# 2SlotElevator.net
KiCad netlist of a schematic drawn in Altium Designer
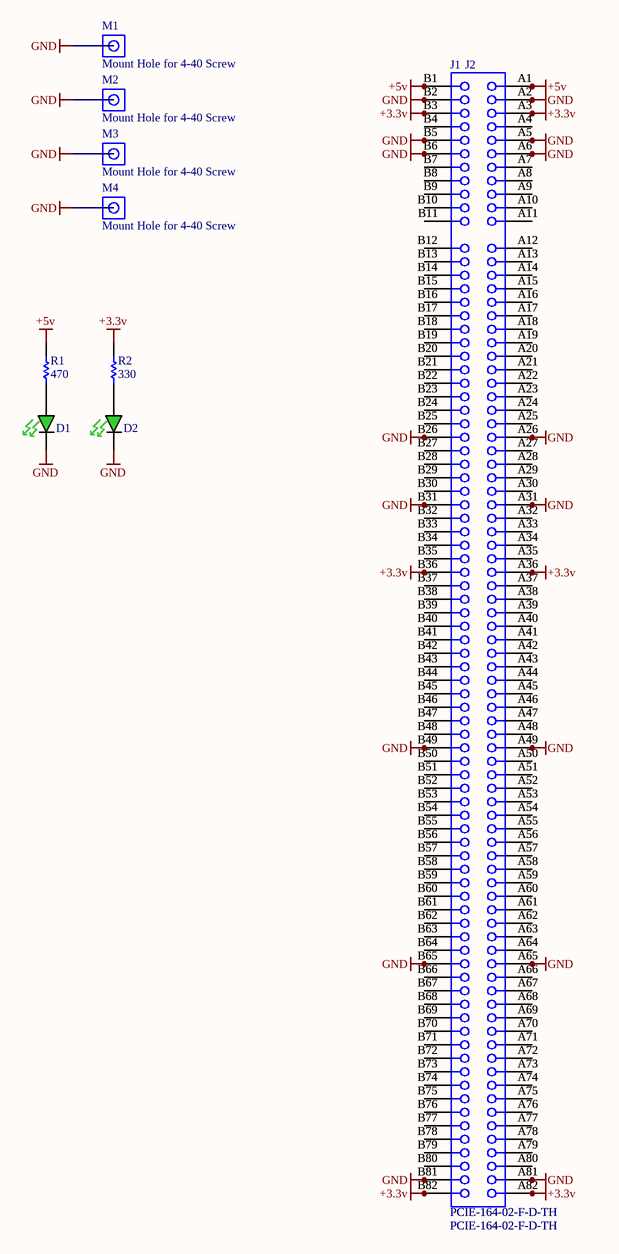
[diagram p0: 2SlotElevator.SchDoc]

(export (version "E")
  (design (tool "Eeschema 10.0.6"))
  (components
    (comp (ref "D1")
      (value "LED 3X1.5MM 568NM GN WTR CLR SMD")
      (footprint "LED_1206 - GREEN")
      (fields
        (field (name "MANUFACTURER") "Kingbright Corp")
        (field (name "MANUFACTURER PART NUMBER") "APL3015SGC-F01")
      )
      (libsource (lib "Diode") (part "APL3015SGC-F01"))
    )
    (comp (ref "D2")
      (value "LED 3X1.5MM 568NM GN WTR CLR SMD")
      (footprint "LED_1206 - GREEN")
      (fields
        (field (name "MANUFACTURER") "Kingbright Corp")
        (field (name "MANUFACTURER PART NUMBER") "APL3015SGC-F01")
      )
      (libsource (lib "Diode") (part "APL3015SGC-F01"))
    )
    (comp (ref "J1")
      (value "PCIE-164-02-F-D-TH")
      (footprint "PCIE-164-02-F-D-TH")
      (description "SAMTEC - PCIE-164-02-F-D-TH - SOCKET, PCI-E, 2X82")
      (fields (field (name "MANUFACTURER") "SAMTEC") (field (name "ALTIUM_VALUE") "PCIE-164-02-F-D-TH"))
      (libsource (lib "eConnector") (part "PCIE-164-02-F-D-TH"))
    )
    (comp (ref "J2")
      (value "PCIE-164-02-F-D-TH")
      (footprint "PCIE-164-02-F-D-TH")
      (description "SAMTEC - PCIE-164-02-F-D-TH - SOCKET, PCI-E, 2X82")
      (fields (field (name "MANUFACTURER") "SAMTEC") (field (name "ALTIUM_VALUE") "PCIE-164-02-F-D-TH"))
      (libsource (lib "eConnector") (part "PCIE-164-02-F-D-TH"))
    )
    (comp (ref "M1")
      (value "Mount Hole for 4-40 Screw")
      (footprint "4-40 Hole")
      (fields (field (name "SOURCE") "Digikey"))
      (libsource (lib "EMechanical") (part "4-40 Hole"))
    )
    (comp (ref "M2")
      (value "Mount Hole for 4-40 Screw")
      (footprint "4-40 Hole")
      (fields (field (name "SOURCE") "Digikey"))
      (libsource (lib "EMechanical") (part "4-40 Hole"))
    )
    (comp (ref "M3")
      (value "Mount Hole for 4-40 Screw")
      (footprint "4-40 Hole")
      (fields (field (name "SOURCE") "Digikey"))
      (libsource (lib "EMechanical") (part "4-40 Hole"))
    )
    (comp (ref "M4")
      (value "Mount Hole for 4-40 Screw")
      (footprint "4-40 Hole")
      (fields (field (name "SOURCE") "Digikey"))
      (libsource (lib "EMechanical") (part "4-40 Hole"))
    )
    (comp (ref "R1")
      (value "470")
      (footprint "R0603")
      (description "RES 470 OHM 1/10W 1% 0603 SMD")
      (fields
        (field (name "MANUFACTURER") "Panasonic - ECG")
        (field (name "MANUFACTURER PART NUMBER") "ERJ-3EKF4700V")
      )
      (libsource (lib "eRCL") (part "ERJ-3EKF4700V"))
    )
    (comp (ref "R2")
      (value "330")
      (footprint "R0603")
      (description "RES 330 OHM 1/10W 1% 0603 SMD")
      (fields
        (field (name "MANUFACTURER") "Panasonic - ECG")
        (field (name "MANUFACTURER PART NUMBER") "ERJ-3EKF3300V")
      )
      (libsource (lib "eRCL") (part "ERJ-3EKF3300V"))
    )
  )
  (nets
    (net (code "1") (name "+3.3v") (class "Default")
      (node (ref "J1") (pin "A3") (pinfunction "A3_A3") (pintype "passive"))
      (node (ref "J1") (pin "A36") (pinfunction "A36_A36") (pintype "passive"))
      (node (ref "J1") (pin "A82") (pinfunction "A82_A82") (pintype "passive"))
      (node (ref "J1") (pin "B3") (pinfunction "B3_B3") (pintype "passive"))
      (node (ref "J1") (pin "B36") (pinfunction "B36_B36") (pintype "passive"))
      (node (ref "J1") (pin "B82") (pinfunction "B82_B82") (pintype "passive"))
      (node (ref "J2") (pin "A3") (pinfunction "A3_A3") (pintype "passive"))
      (node (ref "J2") (pin "A36") (pinfunction "A36_A36") (pintype "passive"))
      (node (ref "J2") (pin "A82") (pinfunction "A82_A82") (pintype "passive"))
      (node (ref "J2") (pin "B3") (pinfunction "B3_B3") (pintype "passive"))
      (node (ref "J2") (pin "B36") (pinfunction "B36_B36") (pintype "passive"))
      (node (ref "J2") (pin "B82") (pinfunction "B82_B82") (pintype "passive"))
      (node (ref "R2") (pin "2") (pinfunction "2_2") (pintype "passive"))
    )
    (net (code "2") (name "+5v") (class "Default")
      (node (ref "J1") (pin "A1") (pinfunction "A1_A1") (pintype "passive"))
      (node (ref "J1") (pin "B1") (pinfunction "B1_B1") (pintype "passive"))
      (node (ref "J2") (pin "A1") (pinfunction "A1_A1") (pintype "passive"))
      (node (ref "J2") (pin "B1") (pinfunction "B1_B1") (pintype "passive"))
      (node (ref "R1") (pin "2") (pinfunction "2_2") (pintype "passive"))
    )
    (net (code "3") (name "GND") (class "Default")
      (node (ref "D1") (pin "C") (pinfunction "C_C") (pintype "passive"))
      (node (ref "D2") (pin "C") (pinfunction "C_C") (pintype "passive"))
      (node (ref "J1") (pin "A2") (pinfunction "A2_A2") (pintype "passive"))
      (node (ref "J1") (pin "A26") (pinfunction "A26_A26") (pintype "passive"))
      (node (ref "J1") (pin "A31") (pinfunction "A31_A31") (pintype "passive"))
      (node (ref "J1") (pin "A49") (pinfunction "A49_A49") (pintype "passive"))
      (node (ref "J1") (pin "A5") (pinfunction "A5_A5") (pintype "passive"))
      (node (ref "J1") (pin "A6") (pinfunction "A6_A6") (pintype "passive"))
      (node (ref "J1") (pin "A65") (pinfunction "A65_A65") (pintype "passive"))
      (node (ref "J1") (pin "A81") (pinfunction "A81_A81") (pintype "passive"))
      (node (ref "J1") (pin "B2") (pinfunction "B2_B2") (pintype "passive"))
      (node (ref "J1") (pin "B26") (pinfunction "B26_B26") (pintype "passive"))
      (node (ref "J1") (pin "B31") (pinfunction "B31_B31") (pintype "passive"))
      (node (ref "J1") (pin "B49") (pinfunction "B49_B49") (pintype "passive"))
      (node (ref "J1") (pin "B5") (pinfunction "B5_B5") (pintype "passive"))
      (node (ref "J1") (pin "B6") (pinfunction "B6_B6") (pintype "passive"))
      (node (ref "J1") (pin "B65") (pinfunction "B65_B65") (pintype "passive"))
      (node (ref "J1") (pin "B81") (pinfunction "B81_B81") (pintype "passive"))
      (node (ref "J2") (pin "A2") (pinfunction "A2_A2") (pintype "passive"))
      (node (ref "J2") (pin "A26") (pinfunction "A26_A26") (pintype "passive"))
      (node (ref "J2") (pin "A31") (pinfunction "A31_A31") (pintype "passive"))
      (node (ref "J2") (pin "A49") (pinfunction "A49_A49") (pintype "passive"))
      (node (ref "J2") (pin "A5") (pinfunction "A5_A5") (pintype "passive"))
      (node (ref "J2") (pin "A6") (pinfunction "A6_A6") (pintype "passive"))
      (node (ref "J2") (pin "A65") (pinfunction "A65_A65") (pintype "passive"))
      (node (ref "J2") (pin "A81") (pinfunction "A81_A81") (pintype "passive"))
      (node (ref "J2") (pin "B2") (pinfunction "B2_B2") (pintype "passive"))
      (node (ref "J2") (pin "B26") (pinfunction "B26_B26") (pintype "passive"))
      (node (ref "J2") (pin "B31") (pinfunction "B31_B31") (pintype "passive"))
      (node (ref "J2") (pin "B49") (pinfunction "B49_B49") (pintype "passive"))
      (node (ref "J2") (pin "B5") (pinfunction "B5_B5") (pintype "passive"))
      (node (ref "J2") (pin "B6") (pinfunction "B6_B6") (pintype "passive"))
      (node (ref "J2") (pin "B65") (pinfunction "B65_B65") (pintype "passive"))
      (node (ref "J2") (pin "B81") (pinfunction "B81_B81") (pintype "passive"))
      (node (ref "M1") (pin "1") (pinfunction "1_1") (pintype "passive"))
      (node (ref "M2") (pin "1") (pinfunction "1_1") (pintype "passive"))
      (node (ref "M3") (pin "1") (pinfunction "1_1") (pintype "passive"))
      (node (ref "M4") (pin "1") (pinfunction "1_1") (pintype "passive"))
    )
    (net (code "4") (name "Net-(D1-PadA)") (class "Default")
      (node (ref "D1") (pin "A") (pinfunction "A_A") (pintype "passive"))
      (node (ref "R1") (pin "1") (pinfunction "1_1") (pintype "passive"))
    )
    (net (code "5") (name "Net-(D2-PadA)") (class "Default")
      (node (ref "D2") (pin "A") (pinfunction "A_A") (pintype "passive"))
      (node (ref "R2") (pin "1") (pinfunction "1_1") (pintype "passive"))
    )
    (net (code "6") (name "Net-(J1-PadA4)") (class "Default")
      (node (ref "J1") (pin "A4") (pinfunction "A4_A4") (pintype "passive"))
      (node (ref "J2") (pin "A4") (pinfunction "A4_A4") (pintype "passive"))
    )
    (net (code "7") (name "Net-(J1-PadA7)") (class "Default")
      (node (ref "J1") (pin "A7") (pinfunction "A7_A7") (pintype "passive"))
      (node (ref "J2") (pin "A7") (pinfunction "A7_A7") (pintype "passive"))
    )
    (net (code "8") (name "Net-(J1-PadA8)") (class "Default")
      (node (ref "J1") (pin "A8") (pinfunction "A8_A8") (pintype "passive"))
      (node (ref "J2") (pin "A8") (pinfunction "A8_A8") (pintype "passive"))
    )
    (net (code "9") (name "Net-(J1-PadA9)") (class "Default")
      (node (ref "J1") (pin "A9") (pinfunction "A9_A9") (pintype "passive"))
      (node (ref "J2") (pin "A9") (pinfunction "A9_A9") (pintype "passive"))
    )
    (net (code "10") (name "Net-(J1-PadA10)") (class "Default")
      (node (ref "J1") (pin "A10") (pinfunction "A10_A10") (pintype "passive"))
      (node (ref "J2") (pin "A10") (pinfunction "A10_A10") (pintype "passive"))
    )
    (net (code "11") (name "Net-(J1-PadA11)") (class "Default")
      (node (ref "J1") (pin "A11") (pinfunction "A11_A11") (pintype "passive"))
      (node (ref "J2") (pin "A11") (pinfunction "A11_A11") (pintype "passive"))
    )
    (net (code "12") (name "Net-(J1-PadA12)") (class "Default")
      (node (ref "J1") (pin "A12") (pinfunction "A12_A12") (pintype "passive"))
      (node (ref "J2") (pin "A12") (pinfunction "A12_A12") (pintype "passive"))
    )
    (net (code "13") (name "Net-(J1-PadA13)") (class "Default")
      (node (ref "J1") (pin "A13") (pinfunction "A13_A13") (pintype "passive"))
      (node (ref "J2") (pin "A13") (pinfunction "A13_A13") (pintype "passive"))
    )
    (net (code "14") (name "Net-(J1-PadA14)") (class "Default")
      (node (ref "J1") (pin "A14") (pinfunction "A14_A14") (pintype "passive"))
      (node (ref "J2") (pin "A14") (pinfunction "A14_A14") (pintype "passive"))
    )
    (net (code "15") (name "Net-(J1-PadA15)") (class "Default")
      (node (ref "J1") (pin "A15") (pinfunction "A15_A15") (pintype "passive"))
      (node (ref "J2") (pin "A15") (pinfunction "A15_A15") (pintype "passive"))
    )
    (net (code "16") (name "Net-(J1-PadA16)") (class "Default")
      (node (ref "J1") (pin "A16") (pinfunction "A16_A16") (pintype "passive"))
      (node (ref "J2") (pin "A16") (pinfunction "A16_A16") (pintype "passive"))
    )
    (net (code "17") (name "Net-(J1-PadA17)") (class "Default")
      (node (ref "J1") (pin "A17") (pinfunction "A17_A17") (pintype "passive"))
      (node (ref "J2") (pin "A17") (pinfunction "A17_A17") (pintype "passive"))
    )
    (net (code "18") (name "Net-(J1-PadA18)") (class "Default")
      (node (ref "J1") (pin "A18") (pinfunction "A18_A18") (pintype "passive"))
      (node (ref "J2") (pin "A18") (pinfunction "A18_A18") (pintype "passive"))
    )
    (net (code "19") (name "Net-(J1-PadA19)") (class "Default")
      (node (ref "J1") (pin "A19") (pinfunction "A19_A19") (pintype "passive"))
      (node (ref "J2") (pin "A19") (pinfunction "A19_A19") (pintype "passive"))
    )
    (net (code "20") (name "Net-(J1-PadA20)") (class "Default")
      (node (ref "J1") (pin "A20") (pinfunction "A20_A20") (pintype "passive"))
      (node (ref "J2") (pin "A20") (pinfunction "A20_A20") (pintype "passive"))
    )
    (net (code "21") (name "Net-(J1-PadA21)") (class "Default")
      (node (ref "J1") (pin "A21") (pinfunction "A21_A21") (pintype "passive"))
      (node (ref "J2") (pin "A21") (pinfunction "A21_A21") (pintype "passive"))
    )
    (net (code "22") (name "Net-(J1-PadA22)") (class "Default")
      (node (ref "J1") (pin "A22") (pinfunction "A22_A22") (pintype "passive"))
      (node (ref "J2") (pin "A22") (pinfunction "A22_A22") (pintype "passive"))
    )
    (net (code "23") (name "Net-(J1-PadA23)") (class "Default")
      (node (ref "J1") (pin "A23") (pinfunction "A23_A23") (pintype "passive"))
      (node (ref "J2") (pin "A23") (pinfunction "A23_A23") (pintype "passive"))
    )
    (net (code "24") (name "Net-(J1-PadA24)") (class "Default")
      (node (ref "J1") (pin "A24") (pinfunction "A24_A24") (pintype "passive"))
      (node (ref "J2") (pin "A24") (pinfunction "A24_A24") (pintype "passive"))
    )
    (net (code "25") (name "Net-(J1-PadA25)") (class "Default")
      (node (ref "J1") (pin "A25") (pinfunction "A25_A25") (pintype "passive"))
      (node (ref "J2") (pin "A25") (pinfunction "A25_A25") (pintype "passive"))
    )
    (net (code "26") (name "Net-(J1-PadA27)") (class "Default")
      (node (ref "J1") (pin "A27") (pinfunction "A27_A27") (pintype "passive"))
      (node (ref "J2") (pin "A27") (pinfunction "A27_A27") (pintype "passive"))
    )
    (net (code "27") (name "Net-(J1-PadA28)") (class "Default")
      (node (ref "J1") (pin "A28") (pinfunction "A28_A28") (pintype "passive"))
      (node (ref "J2") (pin "A28") (pinfunction "A28_A28") (pintype "passive"))
    )
    (net (code "28") (name "Net-(J1-PadA29)") (class "Default")
      (node (ref "J1") (pin "A29") (pinfunction "A29_A29") (pintype "passive"))
      (node (ref "J2") (pin "A29") (pinfunction "A29_A29") (pintype "passive"))
    )
    (net (code "29") (name "Net-(J1-PadA30)") (class "Default")
      (node (ref "J1") (pin "A30") (pinfunction "A30_A30") (pintype "passive"))
      (node (ref "J2") (pin "A30") (pinfunction "A30_A30") (pintype "passive"))
    )
    (net (code "30") (name "Net-(J1-PadA32)") (class "Default")
      (node (ref "J1") (pin "A32") (pinfunction "A32_A32") (pintype "passive"))
      (node (ref "J2") (pin "A32") (pinfunction "A32_A32") (pintype "passive"))
    )
    (net (code "31") (name "Net-(J1-PadA33)") (class "Default")
      (node (ref "J1") (pin "A33") (pinfunction "A33_A33") (pintype "passive"))
      (node (ref "J2") (pin "A33") (pinfunction "A33_A33") (pintype "passive"))
    )
    (net (code "32") (name "Net-(J1-PadA34)") (class "Default")
      (node (ref "J1") (pin "A34") (pinfunction "A34_A34") (pintype "passive"))
      (node (ref "J2") (pin "A34") (pinfunction "A34_A34") (pintype "passive"))
    )
    (net (code "33") (name "Net-(J1-PadA35)") (class "Default")
      (node (ref "J1") (pin "A35") (pinfunction "A35_A35") (pintype "passive"))
      (node (ref "J2") (pin "A35") (pinfunction "A35_A35") (pintype "passive"))
    )
    (net (code "34") (name "Net-(J1-PadA37)") (class "Default")
      (node (ref "J1") (pin "A37") (pinfunction "A37_A37") (pintype "passive"))
      (node (ref "J2") (pin "A37") (pinfunction "A37_A37") (pintype "passive"))
    )
    (net (code "35") (name "Net-(J1-PadA38)") (class "Default")
      (node (ref "J1") (pin "A38") (pinfunction "A38_A38") (pintype "passive"))
      (node (ref "J2") (pin "A38") (pinfunction "A38_A38") (pintype "passive"))
    )
    (net (code "36") (name "Net-(J1-PadA39)") (class "Default")
      (node (ref "J1") (pin "A39") (pinfunction "A39_A39") (pintype "passive"))
      (node (ref "J2") (pin "A39") (pinfunction "A39_A39") (pintype "passive"))
    )
    (net (code "37") (name "Net-(J1-PadA40)") (class "Default")
      (node (ref "J1") (pin "A40") (pinfunction "A40_A40") (pintype "passive"))
      (node (ref "J2") (pin "A40") (pinfunction "A40_A40") (pintype "passive"))
    )
    (net (code "38") (name "Net-(J1-PadA41)") (class "Default")
      (node (ref "J1") (pin "A41") (pinfunction "A41_A41") (pintype "passive"))
      (node (ref "J2") (pin "A41") (pinfunction "A41_A41") (pintype "passive"))
    )
    (net (code "39") (name "Net-(J1-PadA42)") (class "Default")
      (node (ref "J1") (pin "A42") (pinfunction "A42_A42") (pintype "passive"))
      (node (ref "J2") (pin "A42") (pinfunction "A42_A42") (pintype "passive"))
    )
    (net (code "40") (name "Net-(J1-PadA43)") (class "Default")
      (node (ref "J1") (pin "A43") (pinfunction "A43_A43") (pintype "passive"))
      (node (ref "J2") (pin "A43") (pinfunction "A43_A43") (pintype "passive"))
    )
    (net (code "41") (name "Net-(J1-PadA44)") (class "Default")
      (node (ref "J1") (pin "A44") (pinfunction "A44_A44") (pintype "passive"))
      (node (ref "J2") (pin "A44") (pinfunction "A44_A44") (pintype "passive"))
    )
    (net (code "42") (name "Net-(J1-PadA45)") (class "Default")
      (node (ref "J1") (pin "A45") (pinfunction "A45_A45") (pintype "passive"))
      (node (ref "J2") (pin "A45") (pinfunction "A45_A45") (pintype "passive"))
    )
    (net (code "43") (name "Net-(J1-PadA46)") (class "Default")
      (node (ref "J1") (pin "A46") (pinfunction "A46_A46") (pintype "passive"))
      (node (ref "J2") (pin "A46") (pinfunction "A46_A46") (pintype "passive"))
    )
    (net (code "44") (name "Net-(J1-PadA47)") (class "Default")
      (node (ref "J1") (pin "A47") (pinfunction "A47_A47") (pintype "passive"))
      (node (ref "J2") (pin "A47") (pinfunction "A47_A47") (pintype "passive"))
    )
    (net (code "45") (name "Net-(J1-PadA48)") (class "Default")
      (node (ref "J1") (pin "A48") (pinfunction "A48_A48") (pintype "passive"))
      (node (ref "J2") (pin "A48") (pinfunction "A48_A48") (pintype "passive"))
    )
    (net (code "46") (name "Net-(J1-PadA50)") (class "Default")
      (node (ref "J1") (pin "A50") (pinfunction "A50_A50") (pintype "passive"))
      (node (ref "J2") (pin "A50") (pinfunction "A50_A50") (pintype "passive"))
    )
    (net (code "47") (name "Net-(J1-PadA51)") (class "Default")
      (node (ref "J1") (pin "A51") (pinfunction "A51_A51") (pintype "passive"))
      (node (ref "J2") (pin "A51") (pinfunction "A51_A51") (pintype "passive"))
    )
    (net (code "48") (name "Net-(J1-PadA52)") (class "Default")
      (node (ref "J1") (pin "A52") (pinfunction "A52_A52") (pintype "passive"))
      (node (ref "J2") (pin "A52") (pinfunction "A52_A52") (pintype "passive"))
    )
    (net (code "49") (name "Net-(J1-PadA53)") (class "Default")
      (node (ref "J1") (pin "A53") (pinfunction "A53_A53") (pintype "passive"))
      (node (ref "J2") (pin "A53") (pinfunction "A53_A53") (pintype "passive"))
    )
    (net (code "50") (name "Net-(J1-PadA54)") (class "Default")
      (node (ref "J1") (pin "A54") (pinfunction "A54_A54") (pintype "passive"))
      (node (ref "J2") (pin "A54") (pinfunction "A54_A54") (pintype "passive"))
    )
    (net (code "51") (name "Net-(J1-PadA55)") (class "Default")
      (node (ref "J1") (pin "A55") (pinfunction "A55_A55") (pintype "passive"))
      (node (ref "J2") (pin "A55") (pinfunction "A55_A55") (pintype "passive"))
    )
    (net (code "52") (name "Net-(J1-PadA56)") (class "Default")
      (node (ref "J1") (pin "A56") (pinfunction "A56_A56") (pintype "passive"))
      (node (ref "J2") (pin "A56") (pinfunction "A56_A56") (pintype "passive"))
    )
    (net (code "53") (name "Net-(J1-PadA57)") (class "Default")
      (node (ref "J1") (pin "A57") (pinfunction "A57_A57") (pintype "passive"))
      (node (ref "J2") (pin "A57") (pinfunction "A57_A57") (pintype "passive"))
    )
    (net (code "54") (name "Net-(J1-PadA58)") (class "Default")
      (node (ref "J1") (pin "A58") (pinfunction "A58_A58") (pintype "passive"))
      (node (ref "J2") (pin "A58") (pinfunction "A58_A58") (pintype "passive"))
    )
    (net (code "55") (name "Net-(J1-PadA59)") (class "Default")
      (node (ref "J1") (pin "A59") (pinfunction "A59_A59") (pintype "passive"))
      (node (ref "J2") (pin "A59") (pinfunction "A59_A59") (pintype "passive"))
    )
    (net (code "56") (name "Net-(J1-PadA60)") (class "Default")
      (node (ref "J1") (pin "A60") (pinfunction "A60_A60") (pintype "passive"))
      (node (ref "J2") (pin "A60") (pinfunction "A60_A60") (pintype "passive"))
    )
    (net (code "57") (name "Net-(J1-PadA61)") (class "Default")
      (node (ref "J1") (pin "A61") (pinfunction "A61_A61") (pintype "passive"))
      (node (ref "J2") (pin "A61") (pinfunction "A61_A61") (pintype "passive"))
    )
    (net (code "58") (name "Net-(J1-PadA62)") (class "Default")
      (node (ref "J1") (pin "A62") (pinfunction "A62_A62") (pintype "passive"))
      (node (ref "J2") (pin "A62") (pinfunction "A62_A62") (pintype "passive"))
    )
    (net (code "59") (name "Net-(J1-PadA63)") (class "Default")
      (node (ref "J1") (pin "A63") (pinfunction "A63_A63") (pintype "passive"))
      (node (ref "J2") (pin "A63") (pinfunction "A63_A63") (pintype "passive"))
    )
    (net (code "60") (name "Net-(J1-PadA64)") (class "Default")
      (node (ref "J1") (pin "A64") (pinfunction "A64_A64") (pintype "passive"))
      (node (ref "J2") (pin "A64") (pinfunction "A64_A64") (pintype "passive"))
    )
    (net (code "61") (name "Net-(J1-PadA66)") (class "Default")
      (node (ref "J1") (pin "A66") (pinfunction "A66_A66") (pintype "passive"))
      (node (ref "J2") (pin "A66") (pinfunction "A66_A66") (pintype "passive"))
    )
    (net (code "62") (name "Net-(J1-PadA67)") (class "Default")
      (node (ref "J1") (pin "A67") (pinfunction "A67_A67") (pintype "passive"))
      (node (ref "J2") (pin "A67") (pinfunction "A67_A67") (pintype "passive"))
    )
    (net (code "63") (name "Net-(J1-PadA68)") (class "Default")
      (node (ref "J1") (pin "A68") (pinfunction "A68_A68") (pintype "passive"))
      (node (ref "J2") (pin "A68") (pinfunction "A68_A68") (pintype "passive"))
    )
    (net (code "64") (name "Net-(J1-PadA69)") (class "Default")
      (node (ref "J1") (pin "A69") (pinfunction "A69_A69") (pintype "passive"))
      (node (ref "J2") (pin "A69") (pinfunction "A69_A69") (pintype "passive"))
    )
    (net (code "65") (name "Net-(J1-PadA70)") (class "Default")
      (node (ref "J1") (pin "A70") (pinfunction "A70_A70") (pintype "passive"))
      (node (ref "J2") (pin "A70") (pinfunction "A70_A70") (pintype "passive"))
    )
    (net (code "66") (name "Net-(J1-PadA71)") (class "Default")
      (node (ref "J1") (pin "A71") (pinfunction "A71_A71") (pintype "passive"))
      (node (ref "J2") (pin "A71") (pinfunction "A71_A71") (pintype "passive"))
    )
    (net (code "67") (name "Net-(J1-PadA72)") (class "Default")
      (node (ref "J1") (pin "A72") (pinfunction "A72_A72") (pintype "passive"))
      (node (ref "J2") (pin "A72") (pinfunction "A72_A72") (pintype "passive"))
    )
    (net (code "68") (name "Net-(J1-PadA73)") (class "Default")
      (node (ref "J1") (pin "A73") (pinfunction "A73_A73") (pintype "passive"))
      (node (ref "J2") (pin "A73") (pinfunction "A73_A73") (pintype "passive"))
    )
    (net (code "69") (name "Net-(J1-PadA74)") (class "Default")
      (node (ref "J1") (pin "A74") (pinfunction "A74_A74") (pintype "passive"))
      (node (ref "J2") (pin "A74") (pinfunction "A74_A74") (pintype "passive"))
    )
    (net (code "70") (name "Net-(J1-PadA75)") (class "Default")
      (node (ref "J1") (pin "A75") (pinfunction "A75_A75") (pintype "passive"))
      (node (ref "J2") (pin "A75") (pinfunction "A75_A75") (pintype "passive"))
    )
    (net (code "71") (name "Net-(J1-PadA76)") (class "Default")
      (node (ref "J1") (pin "A76") (pinfunction "A76_A76") (pintype "passive"))
      (node (ref "J2") (pin "A76") (pinfunction "A76_A76") (pintype "passive"))
    )
    (net (code "72") (name "Net-(J1-PadA77)") (class "Default")
      (node (ref "J1") (pin "A77") (pinfunction "A77_A77") (pintype "passive"))
      (node (ref "J2") (pin "A77") (pinfunction "A77_A77") (pintype "passive"))
    )
    (net (code "73") (name "Net-(J1-PadA78)") (class "Default")
      (node (ref "J1") (pin "A78") (pinfunction "A78_A78") (pintype "passive"))
      (node (ref "J2") (pin "A78") (pinfunction "A78_A78") (pintype "passive"))
    )
    (net (code "74") (name "Net-(J1-PadA79)") (class "Default")
      (node (ref "J1") (pin "A79") (pinfunction "A79_A79") (pintype "passive"))
      (node (ref "J2") (pin "A79") (pinfunction "A79_A79") (pintype "passive"))
    )
    (net (code "75") (name "Net-(J1-PadA80)") (class "Default")
      (node (ref "J1") (pin "A80") (pinfunction "A80_A80") (pintype "passive"))
      (node (ref "J2") (pin "A80") (pinfunction "A80_A80") (pintype "passive"))
    )
    (net (code "76") (name "Net-(J1-PadB4)") (class "Default")
      (node (ref "J1") (pin "B4") (pinfunction "B4_B4") (pintype "passive"))
      (node (ref "J2") (pin "B4") (pinfunction "B4_B4") (pintype "passive"))
    )
    (net (code "77") (name "Net-(J1-PadB7)") (class "Default")
      (node (ref "J1") (pin "B7") (pinfunction "B7_B7") (pintype "passive"))
      (node (ref "J2") (pin "B7") (pinfunction "B7_B7") (pintype "passive"))
    )
    (net (code "78") (name "Net-(J1-PadB8)") (class "Default")
      (node (ref "J1") (pin "B8") (pinfunction "B8_B8") (pintype "passive"))
      (node (ref "J2") (pin "B8") (pinfunction "B8_B8") (pintype "passive"))
    )
    (net (code "79") (name "Net-(J1-PadB9)") (class "Default")
      (node (ref "J1") (pin "B9") (pinfunction "B9_B9") (pintype "passive"))
      (node (ref "J2") (pin "B9") (pinfunction "B9_B9") (pintype "passive"))
    )
    (net (code "80") (name "Net-(J1-PadB10)") (class "Default")
      (node (ref "J1") (pin "B10") (pinfunction "B10_B10") (pintype "passive"))
      (node (ref "J2") (pin "B10") (pinfunction "B10_B10") (pintype "passive"))
    )
    (net (code "81") (name "Net-(J1-PadB11)") (class "Default")
      (node (ref "J1") (pin "B11") (pinfunction "B11_B11") (pintype "passive"))
      (node (ref "J2") (pin "B11") (pinfunction "B11_B11") (pintype "passive"))
    )
    (net (code "82") (name "Net-(J1-PadB12)") (class "Default")
      (node (ref "J1") (pin "B12") (pinfunction "B12_B12") (pintype "passive"))
      (node (ref "J2") (pin "B12") (pinfunction "B12_B12") (pintype "passive"))
    )
    (net (code "83") (name "Net-(J1-PadB13)") (class "Default")
      (node (ref "J1") (pin "B13") (pinfunction "B13_B13") (pintype "passive"))
      (node (ref "J2") (pin "B13") (pinfunction "B13_B13") (pintype "passive"))
    )
    (net (code "84") (name "Net-(J1-PadB14)") (class "Default")
      (node (ref "J1") (pin "B14") (pinfunction "B14_B14") (pintype "passive"))
      (node (ref "J2") (pin "B14") (pinfunction "B14_B14") (pintype "passive"))
    )
    (net (code "85") (name "Net-(J1-PadB15)") (class "Default")
      (node (ref "J1") (pin "B15") (pinfunction "B15_B15") (pintype "passive"))
      (node (ref "J2") (pin "B15") (pinfunction "B15_B15") (pintype "passive"))
    )
    (net (code "86") (name "Net-(J1-PadB16)") (class "Default")
      (node (ref "J1") (pin "B16") (pinfunction "B16_B16") (pintype "passive"))
      (node (ref "J2") (pin "B16") (pinfunction "B16_B16") (pintype "passive"))
    )
    (net (code "87") (name "Net-(J1-PadB17)") (class "Default")
      (node (ref "J1") (pin "B17") (pinfunction "B17_B17") (pintype "passive"))
      (node (ref "J2") (pin "B17") (pinfunction "B17_B17") (pintype "passive"))
    )
    (net (code "88") (name "Net-(J1-PadB18)") (class "Default")
      (node (ref "J1") (pin "B18") (pinfunction "B18_B18") (pintype "passive"))
      (node (ref "J2") (pin "B18") (pinfunction "B18_B18") (pintype "passive"))
    )
    (net (code "89") (name "Net-(J1-PadB19)") (class "Default")
      (node (ref "J1") (pin "B19") (pinfunction "B19_B19") (pintype "passive"))
      (node (ref "J2") (pin "B19") (pinfunction "B19_B19") (pintype "passive"))
    )
    (net (code "90") (name "Net-(J1-PadB20)") (class "Default")
      (node (ref "J1") (pin "B20") (pinfunction "B20_B20") (pintype "passive"))
      (node (ref "J2") (pin "B20") (pinfunction "B20_B20") (pintype "passive"))
    )
    (net (code "91") (name "Net-(J1-PadB21)") (class "Default")
      (node (ref "J1") (pin "B21") (pinfunction "B21_B21") (pintype "passive"))
      (node (ref "J2") (pin "B21") (pinfunction "B21_B21") (pintype "passive"))
    )
    (net (code "92") (name "Net-(J1-PadB22)") (class "Default")
      (node (ref "J1") (pin "B22") (pinfunction "B22_B22") (pintype "passive"))
      (node (ref "J2") (pin "B22") (pinfunction "B22_B22") (pintype "passive"))
    )
    (net (code "93") (name "Net-(J1-PadB23)") (class "Default")
      (node (ref "J1") (pin "B23") (pinfunction "B23_B23") (pintype "passive"))
      (node (ref "J2") (pin "B23") (pinfunction "B23_B23") (pintype "passive"))
    )
    (net (code "94") (name "Net-(J1-PadB24)") (class "Default")
      (node (ref "J1") (pin "B24") (pinfunction "B24_B24") (pintype "passive"))
      (node (ref "J2") (pin "B24") (pinfunction "B24_B24") (pintype "passive"))
    )
    (net (code "95") (name "Net-(J1-PadB25)") (class "Default")
      (node (ref "J1") (pin "B25") (pinfunction "B25_B25") (pintype "passive"))
      (node (ref "J2") (pin "B25") (pinfunction "B25_B25") (pintype "passive"))
    )
    (net (code "96") (name "Net-(J1-PadB27)") (class "Default")
      (node (ref "J1") (pin "B27") (pinfunction "B27_B27") (pintype "passive"))
      (node (ref "J2") (pin "B27") (pinfunction "B27_B27") (pintype "passive"))
    )
    (net (code "97") (name "Net-(J1-PadB28)") (class "Default")
      (node (ref "J1") (pin "B28") (pinfunction "B28_B28") (pintype "passive"))
      (node (ref "J2") (pin "B28") (pinfunction "B28_B28") (pintype "passive"))
    )
    (net (code "98") (name "Net-(J1-PadB29)") (class "Default")
      (node (ref "J1") (pin "B29") (pinfunction "B29_B29") (pintype "passive"))
      (node (ref "J2") (pin "B29") (pinfunction "B29_B29") (pintype "passive"))
    )
    (net (code "99") (name "Net-(J1-PadB30)") (class "Default")
      (node (ref "J1") (pin "B30") (pinfunction "B30_B30") (pintype "passive"))
      (node (ref "J2") (pin "B30") (pinfunction "B30_B30") (pintype "passive"))
    )
    (net (code "100") (name "Net-(J1-PadB32)") (class "Default")
      (node (ref "J1") (pin "B32") (pinfunction "B32_B32") (pintype "passive"))
      (node (ref "J2") (pin "B32") (pinfunction "B32_B32") (pintype "passive"))
    )
    (net (code "101") (name "Net-(J1-PadB33)") (class "Default")
      (node (ref "J1") (pin "B33") (pinfunction "B33_B33") (pintype "passive"))
      (node (ref "J2") (pin "B33") (pinfunction "B33_B33") (pintype "passive"))
    )
    (net (code "102") (name "Net-(J1-PadB34)") (class "Default")
      (node (ref "J1") (pin "B34") (pinfunction "B34_B34") (pintype "passive"))
      (node (ref "J2") (pin "B34") (pinfunction "B34_B34") (pintype "passive"))
    )
    (net (code "103") (name "Net-(J1-PadB35)") (class "Default")
      (node (ref "J1") (pin "B35") (pinfunction "B35_B35") (pintype "passive"))
      (node (ref "J2") (pin "B35") (pinfunction "B35_B35") (pintype "passive"))
    )
    (net (code "104") (name "Net-(J1-PadB37)") (class "Default")
      (node (ref "J1") (pin "B37") (pinfunction "B37_B37") (pintype "passive"))
      (node (ref "J2") (pin "B37") (pinfunction "B37_B37") (pintype "passive"))
    )
    (net (code "105") (name "Net-(J1-PadB38)") (class "Default")
      (node (ref "J1") (pin "B38") (pinfunction "B38_B38") (pintype "passive"))
      (node (ref "J2") (pin "B38") (pinfunction "B38_B38") (pintype "passive"))
    )
    (net (code "106") (name "Net-(J1-PadB39)") (class "Default")
      (node (ref "J1") (pin "B39") (pinfunction "B39_B39") (pintype "passive"))
      (node (ref "J2") (pin "B39") (pinfunction "B39_B39") (pintype "passive"))
    )
    (net (code "107") (name "Net-(J1-PadB40)") (class "Default")
      (node (ref "J1") (pin "B40") (pinfunction "B40_B40") (pintype "passive"))
      (node (ref "J2") (pin "B40") (pinfunction "B40_B40") (pintype "passive"))
    )
    (net (code "108") (name "Net-(J1-PadB41)") (class "Default")
      (node (ref "J1") (pin "B41") (pinfunction "B41_B41") (pintype "passive"))
      (node (ref "J2") (pin "B41") (pinfunction "B41_B41") (pintype "passive"))
    )
    (net (code "109") (name "Net-(J1-PadB42)") (class "Default")
      (node (ref "J1") (pin "B42") (pinfunction "B42_B42") (pintype "passive"))
      (node (ref "J2") (pin "B42") (pinfunction "B42_B42") (pintype "passive"))
    )
    (net (code "110") (name "Net-(J1-PadB43)") (class "Default")
      (node (ref "J1") (pin "B43") (pinfunction "B43_B43") (pintype "passive"))
      (node (ref "J2") (pin "B43") (pinfunction "B43_B43") (pintype "passive"))
    )
    (net (code "111") (name "Net-(J1-PadB44)") (class "Default")
      (node (ref "J1") (pin "B44") (pinfunction "B44_B44") (pintype "passive"))
      (node (ref "J2") (pin "B44") (pinfunction "B44_B44") (pintype "passive"))
    )
    (net (code "112") (name "Net-(J1-PadB45)") (class "Default")
      (node (ref "J1") (pin "B45") (pinfunction "B45_B45") (pintype "passive"))
      (node (ref "J2") (pin "B45") (pinfunction "B45_B45") (pintype "passive"))
    )
    (net (code "113") (name "Net-(J1-PadB46)") (class "Default")
      (node (ref "J1") (pin "B46") (pinfunction "B46_B46") (pintype "passive"))
      (node (ref "J2") (pin "B46") (pinfunction "B46_B46") (pintype "passive"))
    )
    (net (code "114") (name "Net-(J1-PadB47)") (class "Default")
      (node (ref "J1") (pin "B47") (pinfunction "B47_B47") (pintype "passive"))
      (node (ref "J2") (pin "B47") (pinfunction "B47_B47") (pintype "passive"))
    )
    (net (code "115") (name "Net-(J1-PadB48)") (class "Default")
      (node (ref "J1") (pin "B48") (pinfunction "B48_B48") (pintype "passive"))
      (node (ref "J2") (pin "B48") (pinfunction "B48_B48") (pintype "passive"))
    )
    (net (code "116") (name "Net-(J1-PadB50)") (class "Default")
      (node (ref "J1") (pin "B50") (pinfunction "B50_B50") (pintype "passive"))
      (node (ref "J2") (pin "B50") (pinfunction "B50_B50") (pintype "passive"))
    )
    (net (code "117") (name "Net-(J1-PadB51)") (class "Default")
      (node (ref "J1") (pin "B51") (pinfunction "B51_B51") (pintype "passive"))
      (node (ref "J2") (pin "B51") (pinfunction "B51_B51") (pintype "passive"))
    )
    (net (code "118") (name "Net-(J1-PadB52)") (class "Default")
      (node (ref "J1") (pin "B52") (pinfunction "B52_B52") (pintype "passive"))
      (node (ref "J2") (pin "B52") (pinfunction "B52_B52") (pintype "passive"))
    )
    (net (code "119") (name "Net-(J1-PadB53)") (class "Default")
      (node (ref "J1") (pin "B53") (pinfunction "B53_B53") (pintype "passive"))
      (node (ref "J2") (pin "B53") (pinfunction "B53_B53") (pintype "passive"))
    )
    (net (code "120") (name "Net-(J1-PadB54)") (class "Default")
      (node (ref "J1") (pin "B54") (pinfunction "B54_B54") (pintype "passive"))
      (node (ref "J2") (pin "B54") (pinfunction "B54_B54") (pintype "passive"))
    )
    (net (code "121") (name "Net-(J1-PadB55)") (class "Default")
      (node (ref "J1") (pin "B55") (pinfunction "B55_B55") (pintype "passive"))
      (node (ref "J2") (pin "B55") (pinfunction "B55_B55") (pintype "passive"))
    )
    (net (code "122") (name "Net-(J1-PadB56)") (class "Default")
      (node (ref "J1") (pin "B56") (pinfunction "B56_B56") (pintype "passive"))
      (node (ref "J2") (pin "B56") (pinfunction "B56_B56") (pintype "passive"))
    )
    (net (code "123") (name "Net-(J1-PadB57)") (class "Default")
      (node (ref "J1") (pin "B57") (pinfunction "B57_B57") (pintype "passive"))
      (node (ref "J2") (pin "B57") (pinfunction "B57_B57") (pintype "passive"))
    )
    (net (code "124") (name "Net-(J1-PadB58)") (class "Default")
      (node (ref "J1") (pin "B58") (pinfunction "B58_B58") (pintype "passive"))
      (node (ref "J2") (pin "B58") (pinfunction "B58_B58") (pintype "passive"))
    )
    (net (code "125") (name "Net-(J1-PadB59)") (class "Default")
      (node (ref "J1") (pin "B59") (pinfunction "B59_B59") (pintype "passive"))
      (node (ref "J2") (pin "B59") (pinfunction "B59_B59") (pintype "passive"))
    )
    (net (code "126") (name "Net-(J1-PadB60)") (class "Default")
      (node (ref "J1") (pin "B60") (pinfunction "B60_B60") (pintype "passive"))
      (node (ref "J2") (pin "B60") (pinfunction "B60_B60") (pintype "passive"))
    )
    (net (code "127") (name "Net-(J1-PadB61)") (class "Default")
      (node (ref "J1") (pin "B61") (pinfunction "B61_B61") (pintype "passive"))
      (node (ref "J2") (pin "B61") (pinfunction "B61_B61") (pintype "passive"))
    )
    (net (code "128") (name "Net-(J1-PadB62)") (class "Default")
      (node (ref "J1") (pin "B62") (pinfunction "B62_B62") (pintype "passive"))
      (node (ref "J2") (pin "B62") (pinfunction "B62_B62") (pintype "passive"))
    )
    (net (code "129") (name "Net-(J1-PadB63)") (class "Default")
      (node (ref "J1") (pin "B63") (pinfunction "B63_B63") (pintype "passive"))
      (node (ref "J2") (pin "B63") (pinfunction "B63_B63") (pintype "passive"))
    )
    (net (code "130") (name "Net-(J1-PadB64)") (class "Default")
      (node (ref "J1") (pin "B64") (pinfunction "B64_B64") (pintype "passive"))
      (node (ref "J2") (pin "B64") (pinfunction "B64_B64") (pintype "passive"))
    )
    (net (code "131") (name "Net-(J1-PadB66)") (class "Default")
      (node (ref "J1") (pin "B66") (pinfunction "B66_B66") (pintype "passive"))
      (node (ref "J2") (pin "B66") (pinfunction "B66_B66") (pintype "passive"))
    )
    (net (code "132") (name "Net-(J1-PadB67)") (class "Default")
      (node (ref "J1") (pin "B67") (pinfunction "B67_B67") (pintype "passive"))
      (node (ref "J2") (pin "B67") (pinfunction "B67_B67") (pintype "passive"))
    )
    (net (code "133") (name "Net-(J1-PadB68)") (class "Default")
      (node (ref "J1") (pin "B68") (pinfunction "B68_B68") (pintype "passive"))
      (node (ref "J2") (pin "B68") (pinfunction "B68_B68") (pintype "passive"))
    )
    (net (code "134") (name "Net-(J1-PadB69)") (class "Default")
      (node (ref "J1") (pin "B69") (pinfunction "B69_B69") (pintype "passive"))
      (node (ref "J2") (pin "B69") (pinfunction "B69_B69") (pintype "passive"))
    )
    (net (code "135") (name "Net-(J1-PadB70)") (class "Default")
      (node (ref "J1") (pin "B70") (pinfunction "B70_B70") (pintype "passive"))
      (node (ref "J2") (pin "B70") (pinfunction "B70_B70") (pintype "passive"))
    )
    (net (code "136") (name "Net-(J1-PadB71)") (class "Default")
      (node (ref "J1") (pin "B71") (pinfunction "B71_B71") (pintype "passive"))
      (node (ref "J2") (pin "B71") (pinfunction "B71_B71") (pintype "passive"))
    )
    (net (code "137") (name "Net-(J1-PadB72)") (class "Default")
      (node (ref "J1") (pin "B72") (pinfunction "B72_B72") (pintype "passive"))
      (node (ref "J2") (pin "B72") (pinfunction "B72_B72") (pintype "passive"))
    )
    (net (code "138") (name "Net-(J1-PadB73)") (class "Default")
      (node (ref "J1") (pin "B73") (pinfunction "B73_B73") (pintype "passive"))
      (node (ref "J2") (pin "B73") (pinfunction "B73_B73") (pintype "passive"))
    )
    (net (code "139") (name "Net-(J1-PadB74)") (class "Default")
      (node (ref "J1") (pin "B74") (pinfunction "B74_B74") (pintype "passive"))
      (node (ref "J2") (pin "B74") (pinfunction "B74_B74") (pintype "passive"))
    )
    (net (code "140") (name "Net-(J1-PadB75)") (class "Default")
      (node (ref "J1") (pin "B75") (pinfunction "B75_B75") (pintype "passive"))
      (node (ref "J2") (pin "B75") (pinfunction "B75_B75") (pintype "passive"))
    )
    (net (code "141") (name "Net-(J1-PadB76)") (class "Default")
      (node (ref "J1") (pin "B76") (pinfunction "B76_B76") (pintype "passive"))
      (node (ref "J2") (pin "B76") (pinfunction "B76_B76") (pintype "passive"))
    )
    (net (code "142") (name "Net-(J1-PadB77)") (class "Default")
      (node (ref "J1") (pin "B77") (pinfunction "B77_B77") (pintype "passive"))
      (node (ref "J2") (pin "B77") (pinfunction "B77_B77") (pintype "passive"))
    )
    (net (code "143") (name "Net-(J1-PadB78)") (class "Default")
      (node (ref "J1") (pin "B78") (pinfunction "B78_B78") (pintype "passive"))
      (node (ref "J2") (pin "B78") (pinfunction "B78_B78") (pintype "passive"))
    )
    (net (code "144") (name "Net-(J1-PadB79)") (class "Default")
      (node (ref "J1") (pin "B79") (pinfunction "B79_B79") (pintype "passive"))
      (node (ref "J2") (pin "B79") (pinfunction "B79_B79") (pintype "passive"))
    )
    (net (code "145") (name "Net-(J1-PadB80)") (class "Default")
      (node (ref "J1") (pin "B80") (pinfunction "B80_B80") (pintype "passive"))
      (node (ref "J2") (pin "B80") (pinfunction "B80_B80") (pintype "passive"))
    )
  )
)
